# ssm2167_micamp.net
KiCad netlist of a schematic drawn in EAGLE
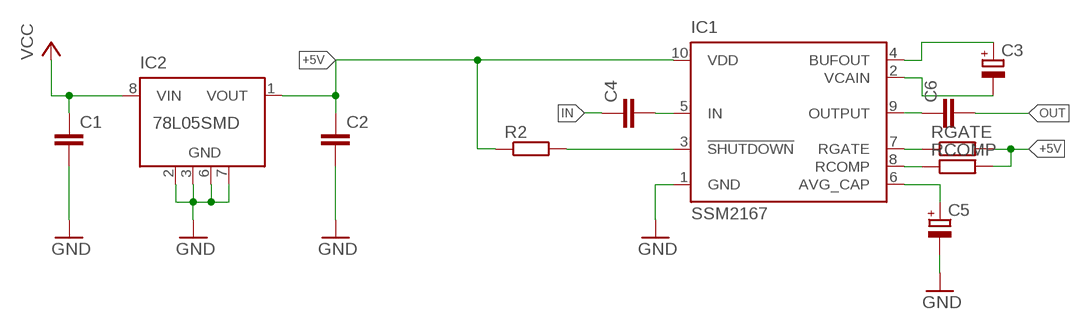
[diagram p0: schematic, sheet 1]

(export (version "E")
  (design (tool "Eeschema 10.0.6"))
  (components
    (comp (ref "C1")
      (value "C-EUC0603K")
      (footprint "eagle-import:C0603K")
      (libsource (lib "eagle-import") (part "C-EUC0603K"))
    )
    (comp (ref "C2")
      (value "C-EUC0603K")
      (footprint "eagle-import:C0603K")
      (libsource (lib "eagle-import") (part "C-EUC0603K"))
    )
    (comp (ref "C3")
      (value "CPOL-EUE")
      (footprint "eagle-import:PANASONIC_E")
      (libsource (lib "eagle-import") (part "CPOL-EUE"))
    )
    (comp (ref "C4")
      (value "C-EUC1812")
      (footprint "eagle-import:C1812")
      (libsource (lib "eagle-import") (part "C-EUC1812"))
    )
    (comp (ref "C5")
      (value "CPOL-EUE")
      (footprint "eagle-import:PANASONIC_E")
      (libsource (lib "eagle-import") (part "CPOL-EUE"))
    )
    (comp (ref "C6")
      (value "C-EUC1812")
      (footprint "eagle-import:C1812")
      (libsource (lib "eagle-import") (part "C-EUC1812"))
    )
    (comp (ref "IC1")
      (value "SSM2167")
      (footprint "eagle-import:SO10")
      (fields (field (name "MPN") "SSM2167Z-EVAL"))
      (libsource (lib "eagle-import") (part "SSM2167"))
    )
    (comp (ref "IC2")
      (value "78L05SMD")
      (footprint "eagle-import:SO08")
      (libsource (lib "eagle-import") (part "78LSMD05"))
    )
    (comp (ref "R2")
      (value "R-EU_M1206")
      (footprint "eagle-import:M1206")
      (libsource (lib "eagle-import") (part "R-EU_M1206"))
    )
    (comp (ref "RCOMP")
      (value "R-EU_M1206")
      (footprint "eagle-import:M1206")
      (libsource (lib "eagle-import") (part "R-EU_M1206"))
    )
    (comp (ref "RGATE")
      (value "R-EU_M1206")
      (footprint "eagle-import:M1206")
      (libsource (lib "eagle-import") (part "R-EU_M1206"))
    )
  )
  (nets
    (net (code "1") (name "+5V") (class "Default")
      (node (ref "C2") (pin "1") (pinfunction "1_1") (pintype "passive"))
      (node (ref "IC1") (pin "10") (pinfunction "VDD_10") (pintype "power_in"))
      (node (ref "IC2") (pin "1") (pinfunction "VOUT_1") (pintype "output"))
      (node (ref "R2") (pin "1") (pinfunction "1_1") (pintype "passive"))
      (node (ref "RCOMP") (pin "2") (pinfunction "2_2") (pintype "passive"))
      (node (ref "RGATE") (pin "2") (pinfunction "2_2") (pintype "passive"))
    )
    (net (code "2") (name "GND") (class "Default")
      (node (ref "C1") (pin "2") (pinfunction "2_2") (pintype "passive"))
      (node (ref "C2") (pin "2") (pinfunction "2_2") (pintype "passive"))
      (node (ref "C5") (pin "-") (pinfunction "-_-") (pintype "passive"))
      (node (ref "IC1") (pin "1") (pinfunction "GND_1") (pintype "power_in"))
      (node (ref "IC2") (pin "2") (pinfunction "GND_2") (pintype "power_in"))
      (node (ref "IC2") (pin "3") (pinfunction "GND_3") (pintype "power_in"))
      (node (ref "IC2") (pin "6") (pinfunction "GND_6") (pintype "power_in"))
      (node (ref "IC2") (pin "7") (pinfunction "GND_7") (pintype "power_in"))
    )
    (net (code "3") (name "IN") (class "Default")
      (node (ref "C4") (pin "1") (pinfunction "1_1") (pintype "passive"))
    )
    (net (code "4") (name "Net-(IC1-AVG_CAP)") (class "Default")
      (node (ref "C5") (pin "+") (pinfunction "+_+") (pintype "passive"))
      (node (ref "IC1") (pin "6") (pinfunction "AVG_CAP_6") (pintype "passive"))
    )
    (net (code "5") (name "Net-(IC1-BUFOUT)") (class "Default")
      (node (ref "C3") (pin "+") (pinfunction "+_+") (pintype "passive"))
      (node (ref "IC1") (pin "4") (pinfunction "BUFOUT_4") (pintype "output"))
    )
    (net (code "6") (name "Net-(IC1-IN)") (class "Default")
      (node (ref "C4") (pin "2") (pinfunction "2_2") (pintype "passive"))
      (node (ref "IC1") (pin "5") (pinfunction "IN_5") (pintype "input"))
    )
    (net (code "7") (name "Net-(IC1-OUTPUT)") (class "Default")
      (node (ref "C6") (pin "1") (pinfunction "1_1") (pintype "passive"))
      (node (ref "IC1") (pin "9") (pinfunction "OUTPUT_9") (pintype "output"))
    )
    (net (code "8") (name "Net-(IC1-RCOMP)") (class "Default")
      (node (ref "IC1") (pin "8") (pinfunction "RCOMP_8") (pintype "passive"))
      (node (ref "RCOMP") (pin "1") (pinfunction "1_1") (pintype "passive"))
    )
    (net (code "9") (name "Net-(IC1-RGATE)") (class "Default")
      (node (ref "IC1") (pin "7") (pinfunction "RGATE_7") (pintype "passive"))
      (node (ref "RGATE") (pin "1") (pinfunction "1_1") (pintype "passive"))
    )
    (net (code "10") (name "Net-(IC1-VCAIN)") (class "Default")
      (node (ref "C3") (pin "-") (pinfunction "-_-") (pintype "passive"))
      (node (ref "IC1") (pin "2") (pinfunction "VCAIN_2") (pintype "input"))
    )
    (net (code "11") (name "Net-(IC1-~{SHUTDOWN})") (class "Default")
      (node (ref "IC1") (pin "3") (pinfunction "~{SHUTDOWN}_3") (pintype "input"))
      (node (ref "R2") (pin "2") (pinfunction "2_2") (pintype "passive"))
    )
    (net (code "12") (name "OUT") (class "Default")
      (node (ref "C6") (pin "2") (pinfunction "2_2") (pintype "passive"))
    )
    (net (code "13") (name "VCC") (class "Default")
      (node (ref "C1") (pin "1") (pinfunction "1_1") (pintype "passive"))
      (node (ref "IC2") (pin "8") (pinfunction "VIN_8") (pintype "passive"))
    )
  )
)
